# Universal-DB9.net
KiCad netlist of a schematic drawn in EasyEDA Pro
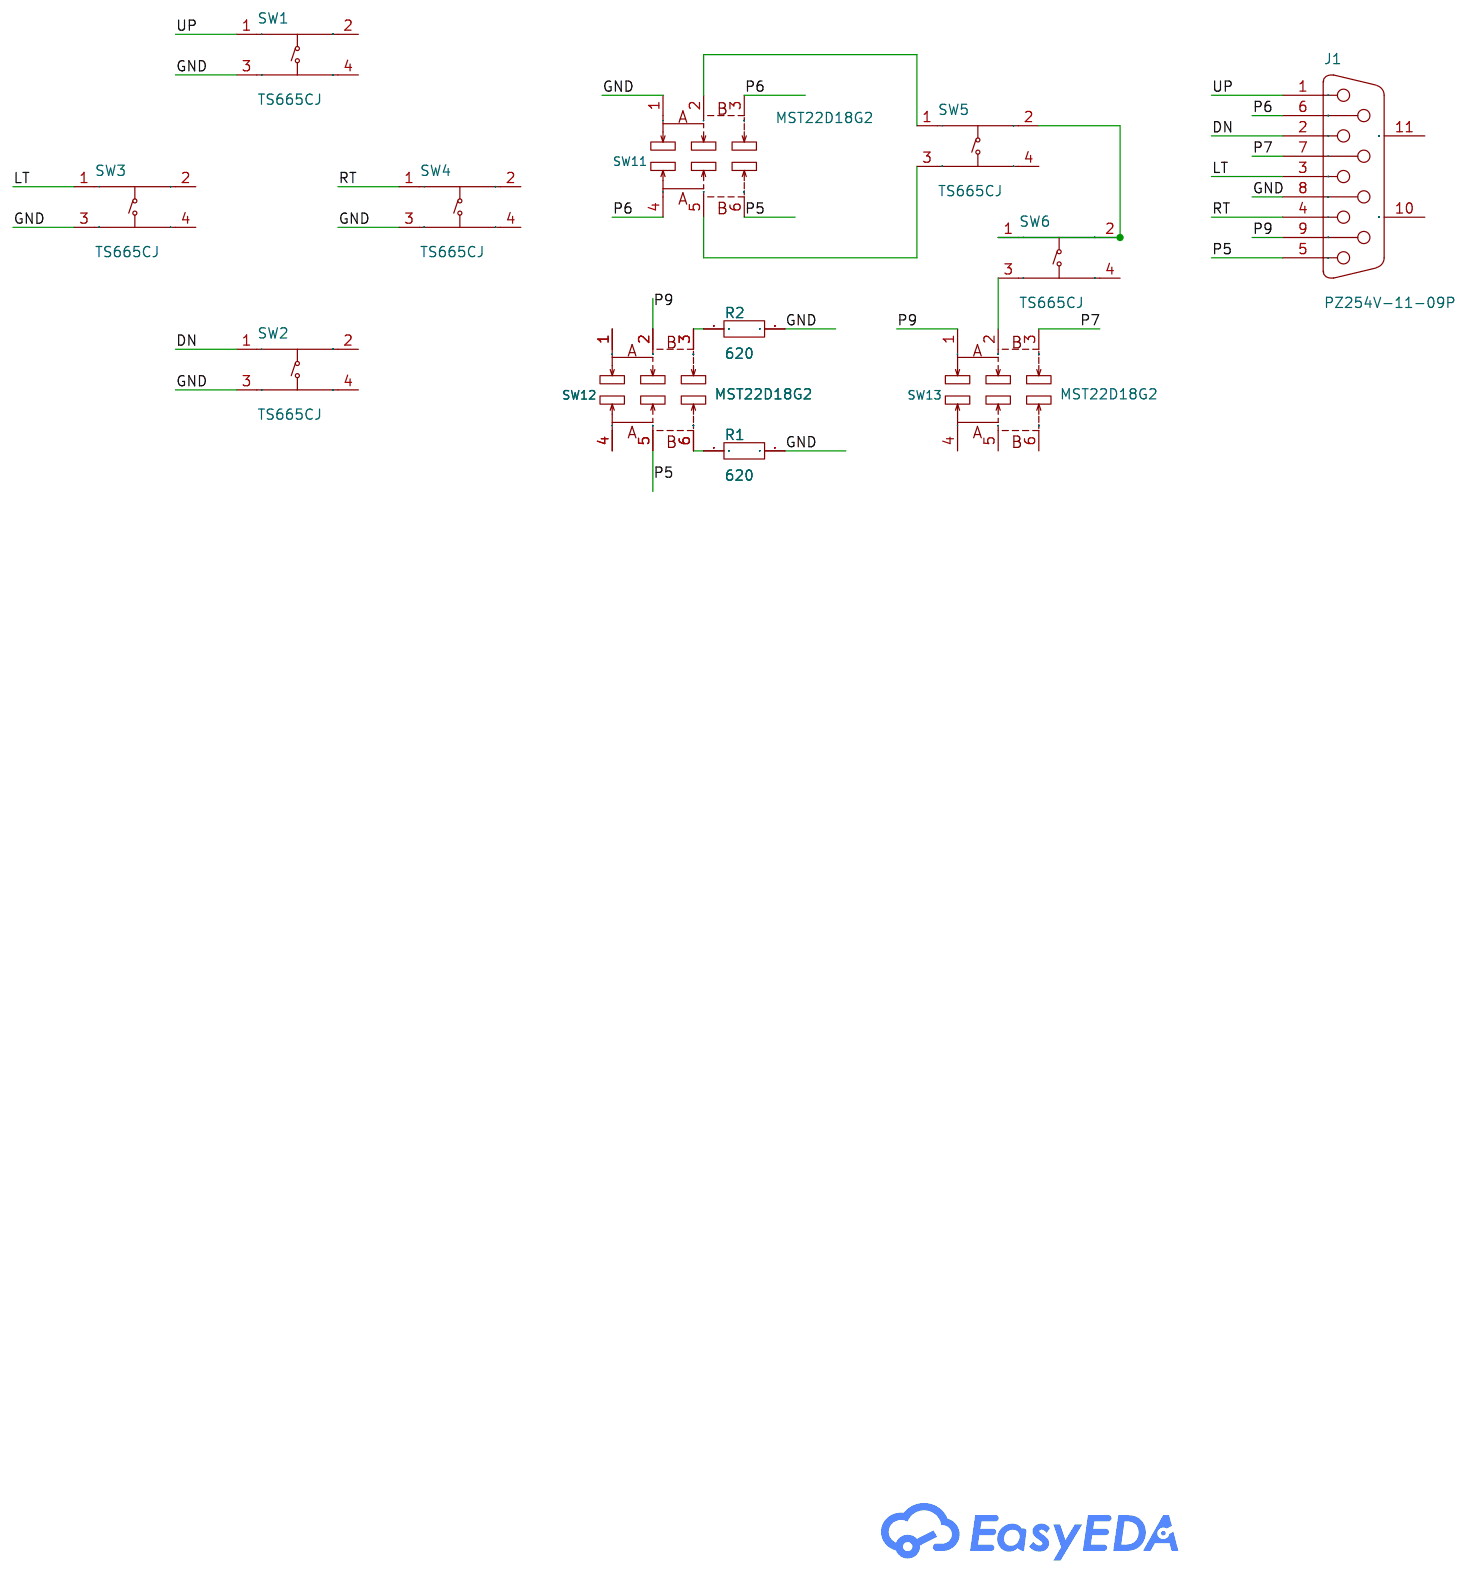
[diagram p0: schematic sheet]

(export (version "E")
  (design (tool "Eeschema 10.0.6"))
  (components
    (comp (ref "J1")
      (value "PZ254V-11-09P")
      (footprint "easyedapro:DSUB-TH_2-5747706-0")
      (fields (field (name "Manufacturer") "XFCN(兴飞)"))
      (libsource (lib "easyedapro") (part "DS1034-09FUNSi44"))
    )
    (comp (ref "R1") (value "620") (footprint "easyedapro:R0603") (libsource (lib "easyedapro") (part "Res")))
    (comp (ref "R2") (value "620") (footprint "easyedapro:R0603") (libsource (lib "easyedapro") (part "Res")))
    (comp (ref "SW1")
      (value "TS665CJ")
      (footprint "easyedapro:SW-TH_4P-L6.0-W6.0-P4.50-LS6.5")
      (fields (field (name "Manufacturer") "SHOU HAN(首韩)"))
      (libsource (lib "easyedapro") (part "TS665CJ"))
    )
    (comp (ref "SW2")
      (value "TS665CJ")
      (footprint "easyedapro:SW-TH_4P-L6.0-W6.0-P4.50-LS6.5")
      (fields (field (name "Manufacturer") "SHOU HAN(首韩)"))
      (libsource (lib "easyedapro") (part "TS665CJ"))
    )
    (comp (ref "SW3")
      (value "TS665CJ")
      (footprint "easyedapro:SW-TH_4P-L6.0-W6.0-P4.50-LS6.5")
      (fields (field (name "Manufacturer") "SHOU HAN(首韩)"))
      (libsource (lib "easyedapro") (part "TS665CJ"))
    )
    (comp (ref "SW4")
      (value "TS665CJ")
      (footprint "easyedapro:SW-TH_4P-L6.0-W6.0-P4.50-LS6.5")
      (fields (field (name "Manufacturer") "SHOU HAN(首韩)"))
      (libsource (lib "easyedapro") (part "TS665CJ"))
    )
    (comp (ref "SW5")
      (value "TS665CJ")
      (footprint "easyedapro:SW-TH_4P-L6.0-W6.0-P4.50-LS6.5")
      (fields (field (name "Manufacturer") "SHOU HAN(首韩)"))
      (libsource (lib "easyedapro") (part "TS665CJ"))
    )
    (comp (ref "SW6")
      (value "TS665CJ")
      (footprint "easyedapro:SW-TH_4P-L6.0-W6.0-P4.50-LS6.5")
      (fields (field (name "Manufacturer") "SHOU HAN(首韩)"))
      (libsource (lib "easyedapro") (part "TS665CJ"))
    )
    (comp (ref "SW11")
      (value "MST22D18G2")
      (footprint "easyedapro:SW-SMD_MST22D18G2")
      (fields (field (name "Manufacturer") "SHOU HAN(首韩)"))
      (libsource (lib "easyedapro") (part "MST22D18G2"))
    )
    (comp (ref "SW12")
      (value "MST22D18G2")
      (footprint "easyedapro:SW-SMD_MST22D18G2")
      (fields (field (name "Manufacturer") "SHOU HAN(首韩)"))
      (libsource (lib "easyedapro") (part "MST22D18G2"))
    )
    (comp (ref "SW13")
      (value "MST22D18G2")
      (footprint "easyedapro:SW-SMD_MST22D18G2")
      (fields (field (name "Manufacturer") "SHOU HAN(首韩)"))
      (libsource (lib "easyedapro") (part "MST22D18G2"))
    )
  )
  (nets
    (net (code "1") (name "/DN") (class "Default")
      (node (ref "J1") (pin "2") (pinfunction "2_2") (pintype "input"))
      (node (ref "SW2") (pin "1") (pinfunction "A_1") (pintype "unspecified"))
    )
    (net (code "2") (name "/GND") (class "Default")
      (node (ref "J1") (pin "8") (pinfunction "8_8") (pintype "input"))
      (node (ref "R1") (pin "2") (pinfunction "2_2") (pintype "input"))
      (node (ref "R2") (pin "2") (pinfunction "2_2") (pintype "input"))
      (node (ref "SW1") (pin "3") (pinfunction "C_3") (pintype "unspecified"))
      (node (ref "SW11") (pin "1") (pinfunction "1_1") (pintype "input"))
      (node (ref "SW2") (pin "3") (pinfunction "C_3") (pintype "unspecified"))
      (node (ref "SW3") (pin "3") (pinfunction "C_3") (pintype "unspecified"))
      (node (ref "SW4") (pin "3") (pinfunction "C_3") (pintype "unspecified"))
    )
    (net (code "3") (name "/LT") (class "Default")
      (node (ref "J1") (pin "3") (pinfunction "3_3") (pintype "input"))
      (node (ref "SW3") (pin "1") (pinfunction "A_1") (pintype "unspecified"))
    )
    (net (code "4") (name "/P5") (class "Default")
      (node (ref "J1") (pin "5") (pinfunction "5_5") (pintype "input"))
      (node (ref "SW11") (pin "6") (pinfunction "6_6") (pintype "input"))
      (node (ref "SW12") (pin "5") (pinfunction "5_5") (pintype "input"))
    )
    (net (code "5") (name "/P6") (class "Default")
      (node (ref "J1") (pin "6") (pinfunction "6_6") (pintype "input"))
      (node (ref "SW11") (pin "3") (pinfunction "3_3") (pintype "input"))
      (node (ref "SW11") (pin "4") (pinfunction "4_4") (pintype "input"))
    )
    (net (code "6") (name "/P7") (class "Default")
      (node (ref "J1") (pin "7") (pinfunction "7_7") (pintype "input"))
      (node (ref "SW13") (pin "3") (pinfunction "3_3") (pintype "input"))
    )
    (net (code "7") (name "/P9") (class "Default")
      (node (ref "J1") (pin "9") (pinfunction "9_9") (pintype "input"))
      (node (ref "SW12") (pin "2") (pinfunction "2_2") (pintype "input"))
      (node (ref "SW13") (pin "1") (pinfunction "1_1") (pintype "input"))
    )
    (net (code "8") (name "/RT") (class "Default")
      (node (ref "J1") (pin "4") (pinfunction "4_4") (pintype "input"))
      (node (ref "SW4") (pin "1") (pinfunction "A_1") (pintype "unspecified"))
    )
    (net (code "9") (name "/UP") (class "Default")
      (node (ref "J1") (pin "1") (pinfunction "1_1") (pintype "input"))
      (node (ref "SW1") (pin "1") (pinfunction "A_1") (pintype "unspecified"))
    )
    (net (code "10") (name "Net-(R1-Pad1)") (class "Default")
      (node (ref "R1") (pin "1") (pinfunction "1_1") (pintype "input"))
      (node (ref "SW12") (pin "6") (pinfunction "6_6") (pintype "input"))
    )
    (net (code "11") (name "Net-(R2-Pad1)") (class "Default")
      (node (ref "R2") (pin "1") (pinfunction "1_1") (pintype "input"))
      (node (ref "SW12") (pin "3") (pinfunction "3_3") (pintype "input"))
    )
    (net (code "12") (name "Net-(SW5-A)") (class "Default")
      (node (ref "SW11") (pin "2") (pinfunction "2_2") (pintype "input"))
      (node (ref "SW5") (pin "1") (pinfunction "A_1") (pintype "unspecified"))
    )
    (net (code "13") (name "Net-(SW5-B)") (class "Default")
      (node (ref "SW5") (pin "2") (pinfunction "B_2") (pintype "unspecified"))
      (node (ref "SW6") (pin "1") (pinfunction "A_1") (pintype "unspecified"))
      (node (ref "SW6") (pin "2") (pinfunction "B_2") (pintype "unspecified"))
    )
    (net (code "14") (name "Net-(SW5-C)") (class "Default")
      (node (ref "SW11") (pin "5") (pinfunction "5_5") (pintype "input"))
      (node (ref "SW5") (pin "3") (pinfunction "C_3") (pintype "unspecified"))
    )
    (net (code "15") (name "Net-(SW6-C)") (class "Default")
      (node (ref "SW13") (pin "2") (pinfunction "2_2") (pintype "input"))
      (node (ref "SW6") (pin "3") (pinfunction "C_3") (pintype "unspecified"))
    )
    (net (code "16") (name "unconnected-(J1-MH1-Pad10)") (class "Default")
      (node (ref "J1") (pin "10") (pinfunction "MH1_10") (pintype "input"))
    )
    (net (code "17") (name "unconnected-(J1-MH2-Pad11)") (class "Default")
      (node (ref "J1") (pin "11") (pinfunction "MH2_11") (pintype "input"))
    )
    (net (code "18") (name "unconnected-(SW1-B-Pad2)") (class "Default")
      (node (ref "SW1") (pin "2") (pinfunction "B_2") (pintype "unspecified"))
    )
    (net (code "19") (name "unconnected-(SW1-D-Pad4)") (class "Default")
      (node (ref "SW1") (pin "4") (pinfunction "D_4") (pintype "unspecified"))
    )
    (net (code "20") (name "unconnected-(SW2-B-Pad2)") (class "Default")
      (node (ref "SW2") (pin "2") (pinfunction "B_2") (pintype "unspecified"))
    )
    (net (code "21") (name "unconnected-(SW2-D-Pad4)") (class "Default")
      (node (ref "SW2") (pin "4") (pinfunction "D_4") (pintype "unspecified"))
    )
    (net (code "22") (name "unconnected-(SW3-B-Pad2)") (class "Default")
      (node (ref "SW3") (pin "2") (pinfunction "B_2") (pintype "unspecified"))
    )
    (net (code "23") (name "unconnected-(SW3-D-Pad4)") (class "Default")
      (node (ref "SW3") (pin "4") (pinfunction "D_4") (pintype "unspecified"))
    )
    (net (code "24") (name "unconnected-(SW4-B-Pad2)") (class "Default")
      (node (ref "SW4") (pin "2") (pinfunction "B_2") (pintype "unspecified"))
    )
    (net (code "25") (name "unconnected-(SW4-D-Pad4)") (class "Default")
      (node (ref "SW4") (pin "4") (pinfunction "D_4") (pintype "unspecified"))
    )
    (net (code "26") (name "unconnected-(SW5-D-Pad4)") (class "Default")
      (node (ref "SW5") (pin "4") (pinfunction "D_4") (pintype "unspecified"))
    )
    (net (code "27") (name "unconnected-(SW6-D-Pad4)") (class "Default")
      (node (ref "SW6") (pin "4") (pinfunction "D_4") (pintype "unspecified"))
    )
    (net (code "28") (name "unconnected-(SW12-Pad1)") (class "Default")
      (node (ref "SW12") (pin "1") (pinfunction "1_1") (pintype "input"))
    )
    (net (code "29") (name "unconnected-(SW12-Pad4)") (class "Default")
      (node (ref "SW12") (pin "4") (pinfunction "4_4") (pintype "input"))
    )
    (net (code "30") (name "unconnected-(SW13-Pad4)") (class "Default")
      (node (ref "SW13") (pin "4") (pinfunction "4_4") (pintype "input"))
    )
    (net (code "31") (name "unconnected-(SW13-Pad5)") (class "Default")
      (node (ref "SW13") (pin "5") (pinfunction "5_5") (pintype "input"))
    )
    (net (code "32") (name "unconnected-(SW13-Pad6)") (class "Default")
      (node (ref "SW13") (pin "6") (pinfunction "6_6") (pintype "input"))
    )
  )
)
